# logic.net
KiCad netlist of a schematic drawn in EAGLE
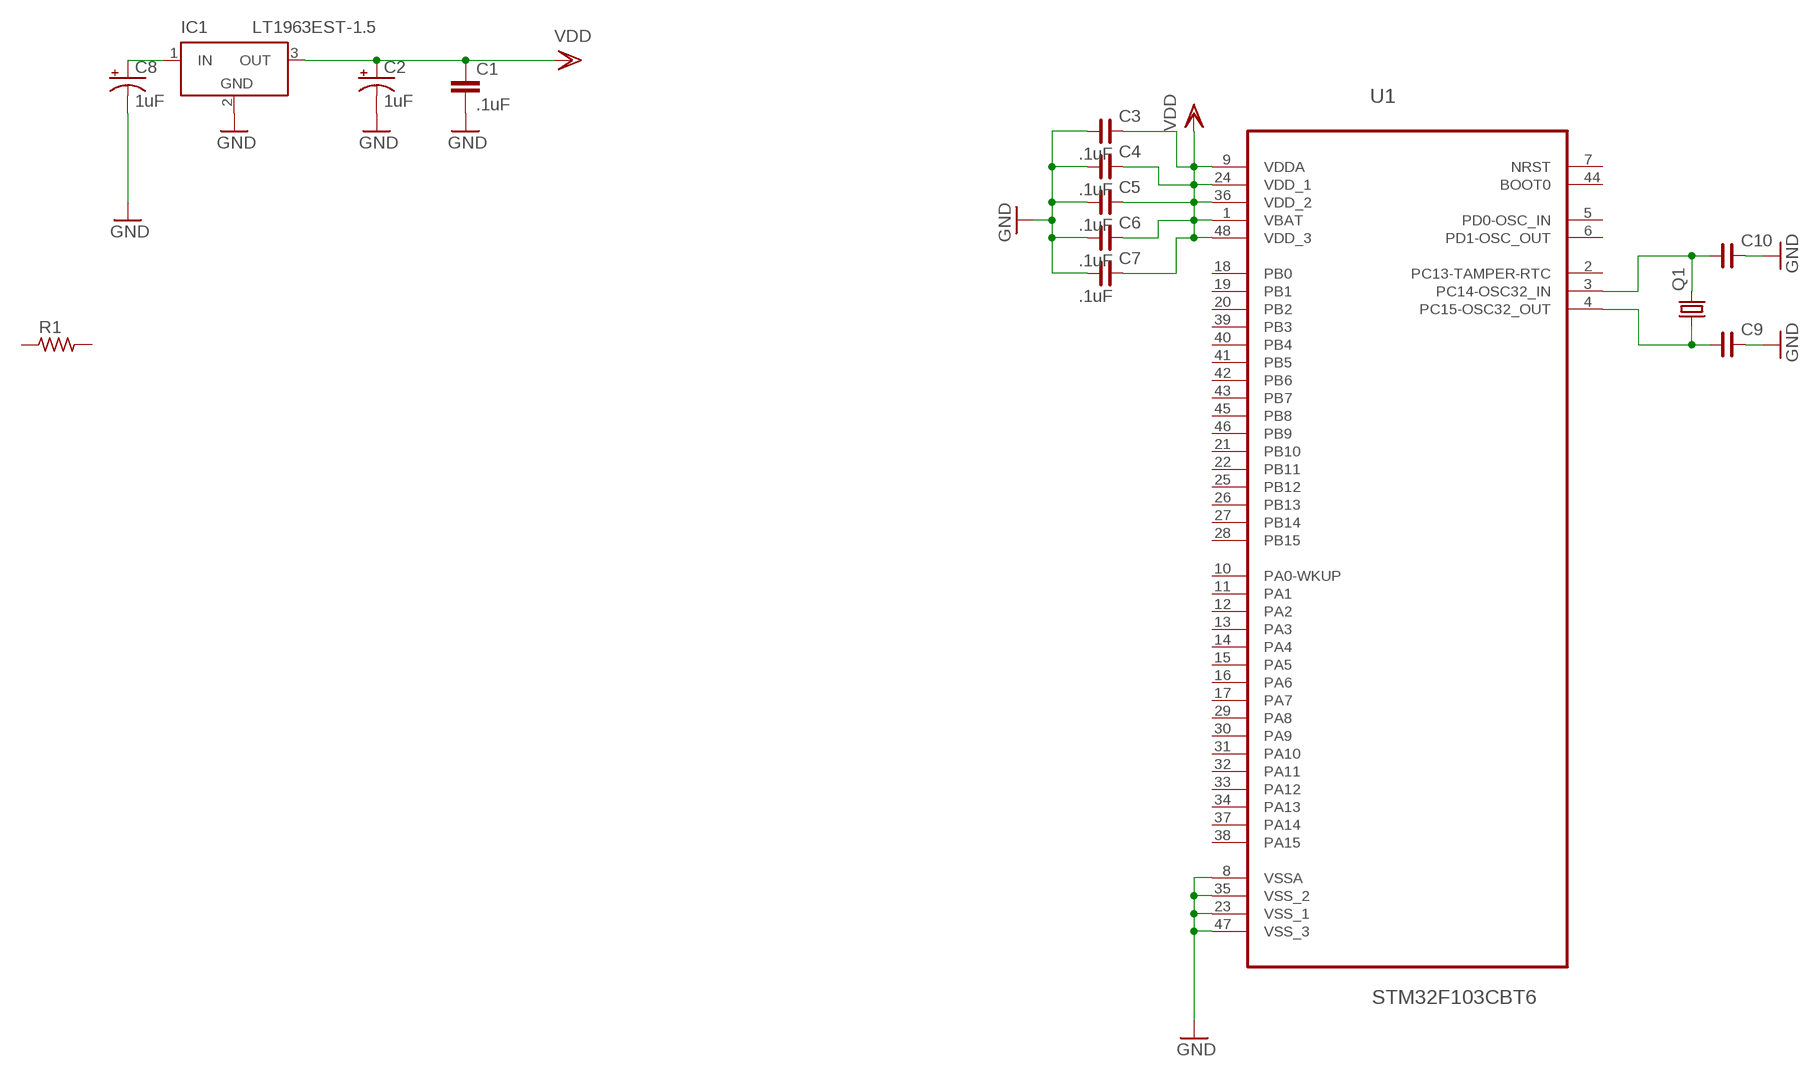
[diagram p0: schematic, sheet 1]

(export (version "E")
  (design (tool "Eeschema 10.0.6"))
  (components
    (comp (ref "C1")
      (value ".1uF")
      (footprint "eagle-import:C0603")
      (libsource (lib "eagle-import") (part "C-EUC0603"))
    )
    (comp (ref "C2")
      (value "1uF")
      (footprint "eagle-import:D_7343-31R")
      (libsource (lib "eagle-import") (part "CPOL-USD/7343-31R"))
    )
    (comp (ref "C3")
      (value ".1uF")
      (footprint "eagle-import:C0402")
      (libsource (lib "eagle-import") (part "C_0402"))
    )
    (comp (ref "C4")
      (value ".1uF")
      (footprint "eagle-import:C0402")
      (libsource (lib "eagle-import") (part "C_0402"))
    )
    (comp (ref "C5")
      (value ".1uF")
      (footprint "eagle-import:C0402")
      (libsource (lib "eagle-import") (part "C_0402"))
    )
    (comp (ref "C6")
      (value ".1uF")
      (footprint "eagle-import:C0402")
      (libsource (lib "eagle-import") (part "C_0402"))
    )
    (comp (ref "C7")
      (value ".1uF")
      (footprint "eagle-import:C0402")
      (libsource (lib "eagle-import") (part "C_0402"))
    )
    (comp (ref "C8")
      (value "1uF")
      (footprint "eagle-import:D_7343-31R")
      (libsource (lib "eagle-import") (part "CPOL-USD/7343-31R"))
    )
    (comp (ref "C9")
      (value "C_0402")
      (footprint "eagle-import:C0402")
      (libsource (lib "eagle-import") (part "C_0402"))
    )
    (comp (ref "C10")
      (value "C_0402")
      (footprint "eagle-import:C0402")
      (libsource (lib "eagle-import") (part "C_0402"))
    )
    (comp (ref "IC1")
      (value "LT1963EST-1.5")
      (footprint "eagle-import:SOT223")
      (libsource (lib "eagle-import") (part "LT1963EST-1.5"))
    )
    (comp (ref "Q1")
      (value "CRYSTALTC26H")
      (footprint "eagle-import:TC26H")
      (libsource (lib "eagle-import") (part "CRYSTALTC26H"))
    )
    (comp (ref "R1")
      (value "R_0402")
      (footprint "eagle-import:R0402")
      (libsource (lib "eagle-import") (part "R_0402"))
    )
    (comp (ref "U1")
      (value "STM32F103CBT6")
      (footprint "eagle-import:QFP50P900X900X160-48N")
      (libsource (lib "eagle-import") (part "STM32F103CBT6"))
    )
  )
  (nets
    (net (code "1") (name "/PA11") (class "Default")
      (node (ref "U1") (pin "32") (pinfunction "PA11_32") (pintype "power_in"))
    )
    (net (code "2") (name "GND") (class "Default")
      (node (ref "C1") (pin "2") (pinfunction "2_2") (pintype "passive"))
      (node (ref "C10") (pin "2") (pinfunction "2_2") (pintype "passive"))
      (node (ref "C2") (pin "-") (pinfunction "-_-") (pintype "passive"))
      (node (ref "C3") (pin "1") (pinfunction "1_1") (pintype "passive"))
      (node (ref "C4") (pin "1") (pinfunction "1_1") (pintype "passive"))
      (node (ref "C5") (pin "1") (pinfunction "1_1") (pintype "passive"))
      (node (ref "C6") (pin "1") (pinfunction "1_1") (pintype "passive"))
      (node (ref "C7") (pin "1") (pinfunction "1_1") (pintype "passive"))
      (node (ref "C8") (pin "-") (pinfunction "-_-") (pintype "passive"))
      (node (ref "C9") (pin "2") (pinfunction "2_2") (pintype "passive"))
      (node (ref "IC1") (pin "2") (pinfunction "GND_2") (pintype "power_in"))
      (node (ref "U1") (pin "23") (pinfunction "VSS_1_23") (pintype "bidirectional"))
      (node (ref "U1") (pin "35") (pinfunction "VSS_2_35") (pintype "passive"))
      (node (ref "U1") (pin "47") (pinfunction "VSS_3_47") (pintype "passive"))
      (node (ref "U1") (pin "8") (pinfunction "VSSA_8") (pintype "passive"))
    )
    (net (code "3") (name "Net-(IC1A-IN)") (class "Default")
      (node (ref "C8") (pin "+") (pinfunction "+_+") (pintype "passive"))
      (node (ref "IC1") (pin "1") (pinfunction "IN_1") (pintype "input"))
    )
    (net (code "4") (name "Net-(U1-PC14-OSC32_IN)") (class "Default")
      (node (ref "C10") (pin "1") (pinfunction "1_1") (pintype "passive"))
      (node (ref "Q1") (pin "2") (pinfunction "2_2") (pintype "passive"))
      (node (ref "U1") (pin "3") (pinfunction "PC14-OSC32_IN_3") (pintype "bidirectional"))
    )
    (net (code "5") (name "Net-(U1-PC15-OSC32_OUT)") (class "Default")
      (node (ref "C9") (pin "1") (pinfunction "1_1") (pintype "passive"))
      (node (ref "Q1") (pin "1") (pinfunction "1_1") (pintype "passive"))
      (node (ref "U1") (pin "4") (pinfunction "PC15-OSC32_OUT_4") (pintype "bidirectional"))
    )
    (net (code "6") (name "VDD") (class "Default")
      (node (ref "C1") (pin "1") (pinfunction "1_1") (pintype "passive"))
      (node (ref "C2") (pin "+") (pinfunction "+_+") (pintype "passive"))
      (node (ref "C3") (pin "2") (pinfunction "2_2") (pintype "passive"))
      (node (ref "C4") (pin "2") (pinfunction "2_2") (pintype "passive"))
      (node (ref "C5") (pin "2") (pinfunction "2_2") (pintype "passive"))
      (node (ref "C6") (pin "2") (pinfunction "2_2") (pintype "passive"))
      (node (ref "C7") (pin "2") (pinfunction "2_2") (pintype "passive"))
      (node (ref "IC1") (pin "3") (pinfunction "OUT_3") (pintype "output"))
      (node (ref "U1") (pin "1") (pinfunction "VBAT_1") (pintype "input"))
      (node (ref "U1") (pin "24") (pinfunction "VDD_1_24") (pintype "bidirectional"))
      (node (ref "U1") (pin "36") (pinfunction "VDD_2_36") (pintype "power_in"))
      (node (ref "U1") (pin "48") (pinfunction "VDD_3_48") (pintype "power_in"))
      (node (ref "U1") (pin "9") (pinfunction "VDDA_9") (pintype "power_in"))
    )
    (net (code "7") (name "unconnected-(R1-Pad1)") (class "Default")
      (node (ref "R1") (pin "1") (pinfunction "1_1") (pintype "passive"))
    )
    (net (code "8") (name "unconnected-(R1-Pad2)") (class "Default")
      (node (ref "R1") (pin "2") (pinfunction "2_2") (pintype "passive"))
    )
    (net (code "9") (name "unconnected-(U1-BOOT0-Pad44)") (class "Default")
      (node (ref "U1") (pin "44") (pinfunction "BOOT0_44") (pintype "bidirectional"))
    )
    (net (code "10") (name "unconnected-(U1-NRST-Pad7)") (class "Default")
      (node (ref "U1") (pin "7") (pinfunction "NRST_7") (pintype "bidirectional"))
    )
    (net (code "11") (name "unconnected-(U1-PA0-WKUP-Pad10)") (class "Default")
      (node (ref "U1") (pin "10") (pinfunction "PA0-WKUP_10") (pintype "bidirectional"))
    )
    (net (code "12") (name "unconnected-(U1-PA1-Pad11)") (class "Default")
      (node (ref "U1") (pin "11") (pinfunction "PA1_11") (pintype "bidirectional"))
    )
    (net (code "13") (name "unconnected-(U1-PA2-Pad12)") (class "Default")
      (node (ref "U1") (pin "12") (pinfunction "PA2_12") (pintype "bidirectional"))
    )
    (net (code "14") (name "unconnected-(U1-PA3-Pad13)") (class "Default")
      (node (ref "U1") (pin "13") (pinfunction "PA3_13") (pintype "bidirectional"))
    )
    (net (code "15") (name "unconnected-(U1-PA4-Pad14)") (class "Default")
      (node (ref "U1") (pin "14") (pinfunction "PA4_14") (pintype "bidirectional"))
    )
    (net (code "16") (name "unconnected-(U1-PA5-Pad15)") (class "Default")
      (node (ref "U1") (pin "15") (pinfunction "PA5_15") (pintype "bidirectional"))
    )
    (net (code "17") (name "unconnected-(U1-PA6-Pad16)") (class "Default")
      (node (ref "U1") (pin "16") (pinfunction "PA6_16") (pintype "bidirectional"))
    )
    (net (code "18") (name "unconnected-(U1-PA7-Pad17)") (class "Default")
      (node (ref "U1") (pin "17") (pinfunction "PA7_17") (pintype "bidirectional"))
    )
    (net (code "19") (name "unconnected-(U1-PA8-Pad29)") (class "Default")
      (node (ref "U1") (pin "29") (pinfunction "PA8_29") (pintype "bidirectional"))
    )
    (net (code "20") (name "unconnected-(U1-PA9-Pad30)") (class "Default")
      (node (ref "U1") (pin "30") (pinfunction "PA9_30") (pintype "bidirectional"))
    )
    (net (code "21") (name "unconnected-(U1-PA10-Pad31)") (class "Default")
      (node (ref "U1") (pin "31") (pinfunction "PA10_31") (pintype "bidirectional"))
    )
    (net (code "22") (name "unconnected-(U1-PA12-Pad33)") (class "Default")
      (node (ref "U1") (pin "33") (pinfunction "PA12_33") (pintype "bidirectional"))
    )
    (net (code "23") (name "unconnected-(U1-PA13-Pad34)") (class "Default")
      (node (ref "U1") (pin "34") (pinfunction "PA13_34") (pintype "bidirectional"))
    )
    (net (code "24") (name "unconnected-(U1-PA14-Pad37)") (class "Default")
      (node (ref "U1") (pin "37") (pinfunction "PA14_37") (pintype "bidirectional"))
    )
    (net (code "25") (name "unconnected-(U1-PA15-Pad38)") (class "Default")
      (node (ref "U1") (pin "38") (pinfunction "PA15_38") (pintype "bidirectional"))
    )
    (net (code "26") (name "unconnected-(U1-PB0-Pad18)") (class "Default")
      (node (ref "U1") (pin "18") (pinfunction "PB0_18") (pintype "bidirectional"))
    )
    (net (code "27") (name "unconnected-(U1-PB1-Pad19)") (class "Default")
      (node (ref "U1") (pin "19") (pinfunction "PB1_19") (pintype "bidirectional"))
    )
    (net (code "28") (name "unconnected-(U1-PB2-Pad20)") (class "Default")
      (node (ref "U1") (pin "20") (pinfunction "PB2_20") (pintype "bidirectional"))
    )
    (net (code "29") (name "unconnected-(U1-PB3-Pad39)") (class "Default")
      (node (ref "U1") (pin "39") (pinfunction "PB3_39") (pintype "bidirectional"))
    )
    (net (code "30") (name "unconnected-(U1-PB4-Pad40)") (class "Default")
      (node (ref "U1") (pin "40") (pinfunction "PB4_40") (pintype "bidirectional"))
    )
    (net (code "31") (name "unconnected-(U1-PB5-Pad41)") (class "Default")
      (node (ref "U1") (pin "41") (pinfunction "PB5_41") (pintype "bidirectional"))
    )
    (net (code "32") (name "unconnected-(U1-PB6-Pad42)") (class "Default")
      (node (ref "U1") (pin "42") (pinfunction "PB6_42") (pintype "bidirectional"))
    )
    (net (code "33") (name "unconnected-(U1-PB7-Pad43)") (class "Default")
      (node (ref "U1") (pin "43") (pinfunction "PB7_43") (pintype "bidirectional"))
    )
    (net (code "34") (name "unconnected-(U1-PB8-Pad45)") (class "Default")
      (node (ref "U1") (pin "45") (pinfunction "PB8_45") (pintype "bidirectional"))
    )
    (net (code "35") (name "unconnected-(U1-PB9-Pad46)") (class "Default")
      (node (ref "U1") (pin "46") (pinfunction "PB9_46") (pintype "bidirectional"))
    )
    (net (code "36") (name "unconnected-(U1-PB10-Pad21)") (class "Default")
      (node (ref "U1") (pin "21") (pinfunction "PB10_21") (pintype "bidirectional"))
    )
    (net (code "37") (name "unconnected-(U1-PB11-Pad22)") (class "Default")
      (node (ref "U1") (pin "22") (pinfunction "PB11_22") (pintype "bidirectional"))
    )
    (net (code "38") (name "unconnected-(U1-PB12-Pad25)") (class "Default")
      (node (ref "U1") (pin "25") (pinfunction "PB12_25") (pintype "bidirectional"))
    )
    (net (code "39") (name "unconnected-(U1-PB13-Pad26)") (class "Default")
      (node (ref "U1") (pin "26") (pinfunction "PB13_26") (pintype "bidirectional"))
    )
    (net (code "40") (name "unconnected-(U1-PB14-Pad27)") (class "Default")
      (node (ref "U1") (pin "27") (pinfunction "PB14_27") (pintype "bidirectional"))
    )
    (net (code "41") (name "unconnected-(U1-PB15-Pad28)") (class "Default")
      (node (ref "U1") (pin "28") (pinfunction "PB15_28") (pintype "bidirectional"))
    )
    (net (code "42") (name "unconnected-(U1-PC13-TAMPER-RTC-Pad2)") (class "Default")
      (node (ref "U1") (pin "2") (pinfunction "PC13-TAMPER-RTC_2") (pintype "bidirectional"))
    )
    (net (code "43") (name "unconnected-(U1-PD0-OSC_IN-Pad5)") (class "Default")
      (node (ref "U1") (pin "5") (pinfunction "PD0-OSC_IN_5") (pintype "bidirectional"))
    )
    (net (code "44") (name "unconnected-(U1-PD1-OSC_OUT-Pad6)") (class "Default")
      (node (ref "U1") (pin "6") (pinfunction "PD1-OSC_OUT_6") (pintype "bidirectional"))
    )
  )
)
